# cpu.net
KiCad netlist of a schematic drawn in Altium Designer
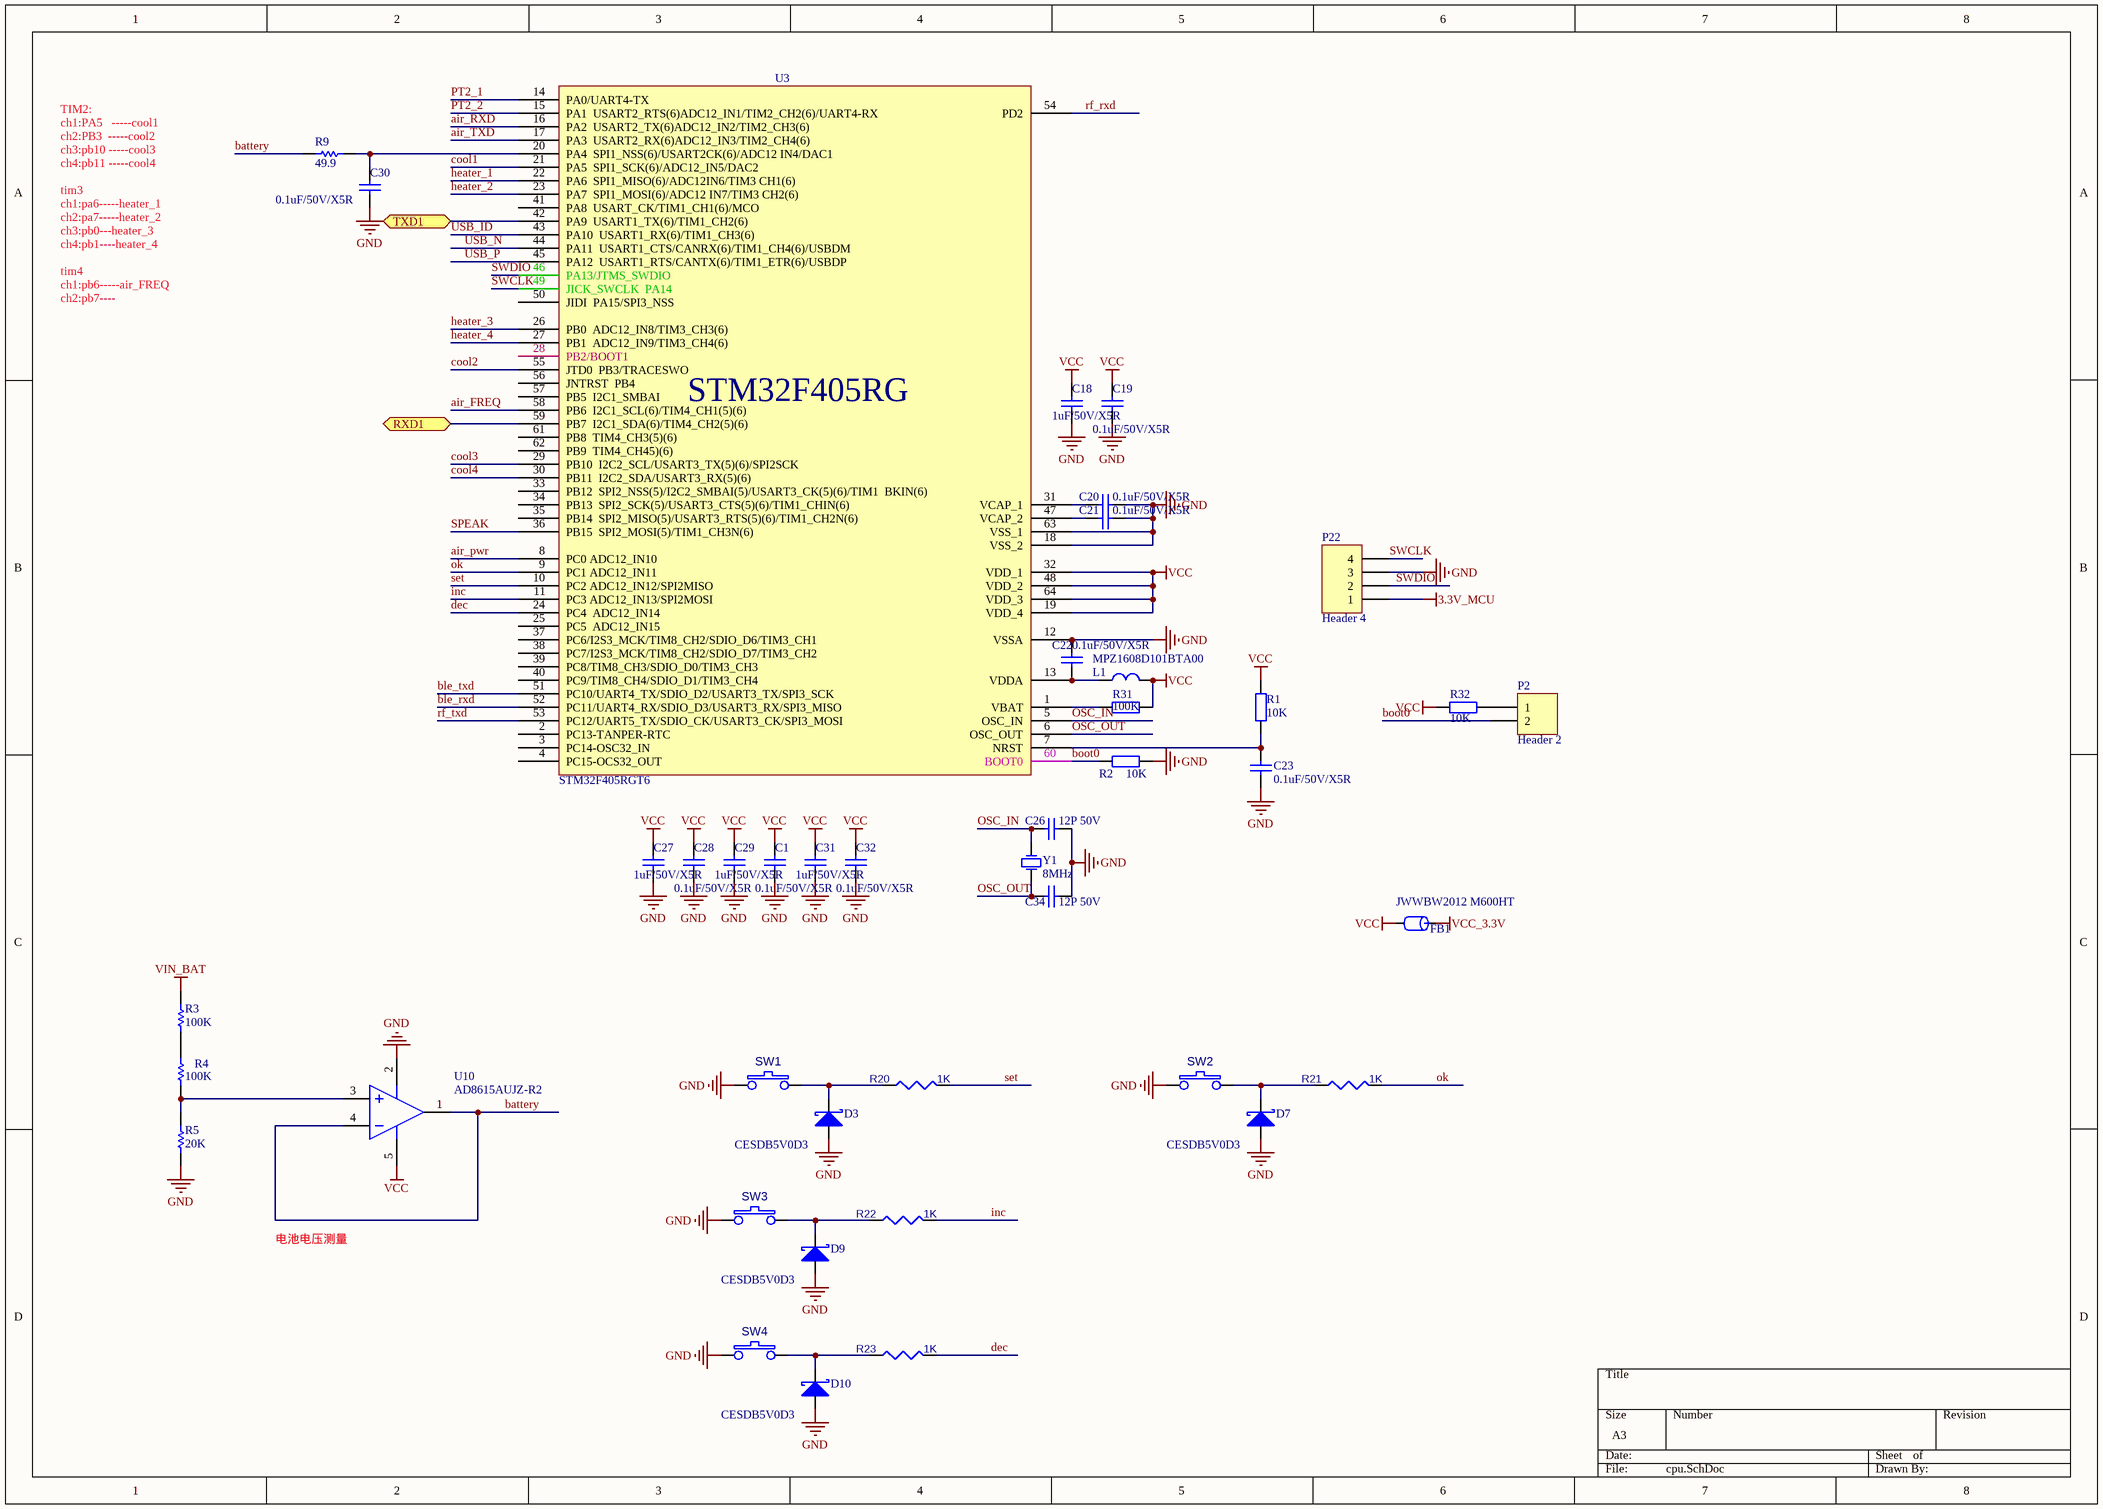
[diagram p0: cpu.SchDoc]

(export (version "E")
  (design (tool "Eeschema 10.0.6"))
  (components
    (comp (ref "C1")
      (value "0.1uF/50V/X5R")
      (footprint "0603C")
      (description "贴片电容 20%")
      (libsource (lib "XiaoyI") (part "CAP4"))
    )
    (comp (ref "C18")
      (value "1uF/50V/X5R")
      (footprint "0603C")
      (description "贴片电容 20%")
      (libsource (lib "XiaoyI") (part "CAP4"))
    )
    (comp (ref "C19")
      (value "0.1uF/50V/X5R")
      (footprint "0603C")
      (description "贴片电容 20%")
      (libsource (lib "XiaoyI") (part "CAP4"))
    )
    (comp (ref "C20")
      (value "0.1uF/50V/X5R")
      (footprint "0603C")
      (description "贴片电容 20%")
      (libsource (lib "XiaoyI") (part "CAP4"))
    )
    (comp (ref "C21")
      (value "0.1uF/50V/X5R")
      (footprint "0603C")
      (description "贴片电容 20%")
      (libsource (lib "XiaoyI") (part "CAP4"))
    )
    (comp (ref "C22")
      (value "0.1uF/50V/X5R")
      (footprint "0603C")
      (description "贴片电容 20%")
      (libsource (lib "XiaoyI") (part "CAP4"))
    )
    (comp (ref "C23")
      (value "0.1uF/50V/X5R")
      (footprint "0603C")
      (description "贴片电容 20%")
      (libsource (lib "XiaoyI") (part "CAP4"))
    )
    (comp (ref "C26")
      (value "12P 50V")
      (footprint "0603C")
      (description "贴片电容 20%")
      (libsource (lib "XiaoyI") (part "CAP4"))
    )
    (comp (ref "C27")
      (value "1uF/50V/X5R")
      (footprint "0603C")
      (description "贴片电容 20%")
      (libsource (lib "XiaoyI") (part "CAP4"))
    )
    (comp (ref "C28")
      (value "0.1uF/50V/X5R")
      (footprint "0603C")
      (description "贴片电容 20%")
      (libsource (lib "XiaoyI") (part "CAP4"))
    )
    (comp (ref "C29")
      (value "1uF/50V/X5R")
      (footprint "0603C")
      (description "贴片电容 20%")
      (libsource (lib "XiaoyI") (part "CAP4"))
    )
    (comp (ref "C30")
      (value "0.1uF/50V/X5R")
      (footprint "0603C")
      (description "贴片电容 20%")
      (libsource (lib "XiaoyI") (part "CAP4"))
    )
    (comp (ref "C31")
      (value "1uF/50V/X5R")
      (footprint "0603C")
      (description "贴片电容 20%")
      (libsource (lib "XiaoyI") (part "CAP4"))
    )
    (comp (ref "C32")
      (value "0.1uF/50V/X5R")
      (footprint "0603C")
      (description "贴片电容 20%")
      (libsource (lib "XiaoyI") (part "CAP4"))
    )
    (comp (ref "C34")
      (value "12P 50V")
      (footprint "0603C")
      (description "贴片电容 20%")
      (libsource (lib "XiaoyI") (part "CAP4"))
    )
    (comp (ref "D3")
      (value "CESDB5V0D3")
      (footprint "SOD323")
      (description "Schottky Diode")
      (libsource (lib "*") (part "DIODE S"))
    )
    (comp (ref "D7")
      (value "CESDB5V0D3")
      (footprint "SOD323")
      (description "Schottky Diode")
      (libsource (lib "*") (part "DIODE S"))
    )
    (comp (ref "D9")
      (value "CESDB5V0D3")
      (footprint "SOD323")
      (description "Schottky Diode")
      (libsource (lib "*") (part "DIODE S"))
    )
    (comp (ref "D10")
      (value "CESDB5V0D3")
      (footprint "SOD323")
      (description "Schottky Diode")
      (libsource (lib "*") (part "DIODE S"))
    )
    (comp (ref "FB1")
      (value "JWWBW2012 M600HT")
      (footprint "0805CZ")
      (libsource (lib "Schlib_20110825") (part "FB"))
    )
    (comp (ref "L1")
      (value "MPZ1608D101BTA00")
      (footprint "0603R")
      (description "磁珠电感 100R 100MHz")
      (libsource (lib "XiaoyI") (part "CIZHU1"))
    )
    (comp (ref "P2")
      (value "Header 2")
      (footprint "HDR1X2")
      (description "Header, 2-Pin")
      (fields (field (name "PUBLISHER") "Altium Limited"))
      (libsource (lib "Miscellaneous Connectors") (part "Header 2"))
    )
    (comp (ref "P22")
      (value "Header 4")
      (footprint "HDR1X4")
      (description "Header, 4-Pin")
      (fields (field (name "PUBLISHER") "Altium Limited"))
      (libsource (lib "Miscellaneous Connectors") (part "Header 4"))
    )
    (comp (ref "R1")
      (value "10K")
      (footprint "0603R")
      (description "贴片电阻 5%")
      (libsource (lib "") (part "RES2_2"))
    )
    (comp (ref "R2")
      (value "10K")
      (footprint "0603R")
      (description "贴片电阻 5%")
      (libsource (lib "XiaoyI") (part "RES2"))
    )
    (comp (ref "R3")
      (value "100K")
      (footprint "0603R")
      (description "Resistor")
      (fields (field (name "PUBLISHER") "Altium Limited"))
      (libsource (lib "Miscellaneous Devices") (part "Res1"))
    )
    (comp (ref "R4")
      (value "100K")
      (footprint "0603R")
      (description "Resistor")
      (fields (field (name "PUBLISHER") "Altium Limited"))
      (libsource (lib "Miscellaneous Devices") (part "Res1"))
    )
    (comp (ref "R5")
      (value "20K")
      (footprint "0603R")
      (description "Resistor")
      (fields (field (name "PUBLISHER") "Altium Limited"))
      (libsource (lib "Miscellaneous Devices") (part "Res1"))
    )
    (comp (ref "R9")
      (value "49.9")
      (footprint "0603R")
      (description "Resistor")
      (fields (field (name "PUBLISHER") "Altium Limited"))
      (libsource (lib "Miscellaneous Devices") (part "Res1"))
    )
    (comp (ref "R20")
      (value "1K")
      (footprint "0603R")
      (fields (field (name "Comment") "1k/1%"))
      (libsource (lib "*") (part "RESISTOR_0"))
    )
    (comp (ref "R21")
      (value "1K")
      (footprint "0603R")
      (fields (field (name "Comment") "1k/1%"))
      (libsource (lib "*") (part "RESISTOR_0"))
    )
    (comp (ref "R22")
      (value "1K")
      (footprint "0603R")
      (fields (field (name "Comment") "1k/1%"))
      (libsource (lib "*") (part "RESISTOR_0"))
    )
    (comp (ref "R23")
      (value "1K")
      (footprint "0603R")
      (fields (field (name "Comment") "1k/1%"))
      (libsource (lib "*") (part "RESISTOR_0"))
    )
    (comp (ref "R31")
      (value "100K")
      (footprint "0603R")
      (description "贴片电阻 5%")
      (libsource (lib "") (part "RES2_1"))
    )
    (comp (ref "R32")
      (value "10K")
      (footprint "0603R")
      (description "贴片电阻 5%")
      (libsource (lib "") (part "RES2_1"))
    )
    (comp (ref "SW1")
      (value "SW PUSHBUTTON")
      (footprint "SW-SMD_L3.9-W3.0-P4.45")
      (libsource (lib "*") (part "SW PUSHBUTTON"))
    )
    (comp (ref "SW2")
      (value "SW PUSHBUTTON")
      (footprint "SW-SMD_L3.9-W3.0-P4.45")
      (libsource (lib "*") (part "SW PUSHBUTTON"))
    )
    (comp (ref "SW3")
      (value "SW PUSHBUTTON")
      (footprint "SW-SMD_L3.9-W3.0-P4.45")
      (libsource (lib "*") (part "SW PUSHBUTTON"))
    )
    (comp (ref "SW4")
      (value "SW PUSHBUTTON")
      (footprint "SW-SMD_L3.9-W3.0-P4.45")
      (libsource (lib "*") (part "SW PUSHBUTTON"))
    )
    (comp (ref "U3")
      (value "STM32F405RGT6")
      (footprint "LQFP-64")
      (description "MCU")
      (libsource (lib "XiaoyI") (part "STM32F405RG"))
    )
    (comp (ref "U10")
      (value "AD8615AUJZ-R2")
      (footprint "sot-23-5")
      (libsource (lib "Schlib1") (part "AD8615"))
    )
    (comp (ref "Y1")
      (value "8MHz")
      (footprint "CRAY_5032")
      (description "晶振")
      (libsource (lib "XiaoyI") (part "XTAL"))
    )
  )
  (nets
    (net (code "1") (name "/OSC_IN") (class "Default")
      (node (ref "C26") (pin "2") (pinfunction "2_2") (pintype "passive"))
      (node (ref "U3") (pin "5") (pinfunction "OSC_IN_5") (pintype "passive"))
      (node (ref "Y1") (pin "2") (pinfunction "OSC2_2") (pintype "passive"))
    )
    (net (code "2") (name "/OSC_OUT") (class "Default")
      (node (ref "C34") (pin "2") (pinfunction "2_2") (pintype "passive"))
      (node (ref "U3") (pin "6") (pinfunction "OSC_OUT_6") (pintype "passive"))
      (node (ref "Y1") (pin "1") (pinfunction "OSC1_1") (pintype "passive"))
    )
    (net (code "3") (name "/PT2_1") (class "Default")
      (node (ref "U3") (pin "14") (pinfunction "PA0/UART4-TX_14") (pintype "passive"))
    )
    (net (code "4") (name "/PT2_2") (class "Default")
      (node (ref "U3") (pin "15") (pinfunction "PA1__USART2_RTS(6)ADC12_IN1/TIM2_CH2(6)/UART4-RX_15") (pintype "passive"))
    )
    (net (code "5") (name "/RXD1") (class "Default")
      (node (ref "U3") (pin "59") (pinfunction "PB7__I2C1_SDA(6)/TIM4_CH2(5)(6)_59") (pintype "passive"))
    )
    (net (code "6") (name "/SPEAK") (class "Default")
      (node (ref "U3") (pin "36") (pinfunction "PB15__SPI2_MOSI(5)/TIM1_CH3N(6)_36") (pintype "passive"))
    )
    (net (code "7") (name "/SWCLK") (class "Default")
      (node (ref "P22") (pin "4") (pinfunction "4_4") (pintype "passive"))
      (node (ref "U3") (pin "49") (pinfunction "JICK_SWCLK__PA14_49") (pintype "passive"))
    )
    (net (code "8") (name "/SWDIO") (class "Default")
      (node (ref "P22") (pin "2") (pinfunction "2_2") (pintype "passive"))
      (node (ref "U3") (pin "46") (pinfunction "PA13/JTMS_SWDIO_46") (pintype "passive"))
    )
    (net (code "9") (name "/TXD1") (class "Default")
      (node (ref "U3") (pin "42") (pinfunction "PA9__USART1_TX(6)/TIM1_CH2(6)_42") (pintype "passive"))
    )
    (net (code "10") (name "/USB_ID") (class "Default")
      (node (ref "U3") (pin "43") (pinfunction "PA10__USART1_RX(6)/TIM1_CH3(6)_43") (pintype "passive"))
    )
    (net (code "11") (name "/USB_N") (class "Default")
      (node (ref "U3") (pin "44") (pinfunction "PA11__USART1_CTS/CANRX(6)/TIM1_CH4(6)/USBDM_44") (pintype "passive"))
    )
    (net (code "12") (name "/USB_P") (class "Default")
      (node (ref "U3") (pin "45") (pinfunction "PA12__USART1_RTS/CANTX(6)/TIM1_ETR(6)/USBDP_45") (pintype "passive"))
    )
    (net (code "13") (name "/air_FREQ") (class "Default")
      (node (ref "U3") (pin "58") (pinfunction "PB6__I2C1_SCL(6)/TIM4_CH1(5)(6)_58") (pintype "passive"))
    )
    (net (code "14") (name "/air_RXD") (class "Default")
      (node (ref "U3") (pin "16") (pinfunction "PA2__USART2_TX(6)ADC12_IN2/TIM2_CH3(6)_16") (pintype "passive"))
    )
    (net (code "15") (name "/air_TXD") (class "Default")
      (node (ref "U3") (pin "17") (pinfunction "PA3__USART2_RX(6)ADC12_IN3/TIM2_CH4(6)_17") (pintype "passive"))
    )
    (net (code "16") (name "/air_pwr") (class "Default")
      (node (ref "U3") (pin "8") (pinfunction "PC0_ADC12_IN10_8") (pintype "passive"))
    )
    (net (code "17") (name "/battery") (class "Default")
      (node (ref "R9") (pin "1") (pinfunction "1_1") (pintype "passive"))
      (node (ref "U10") (pin "1") (pinfunction "OS_NUL_1") (pintype "passive"))
      (node (ref "U10") (pin "4") (pinfunction "V-_4") (pintype "power_in"))
    )
    (net (code "18") (name "/ble_rxd") (class "Default")
      (node (ref "U3") (pin "52") (pinfunction "PC11/UART4_RX/SDIO_D3/USART3_RX/SPI3_MISO_52") (pintype "passive"))
    )
    (net (code "19") (name "/ble_txd") (class "Default")
      (node (ref "U3") (pin "51") (pinfunction "PC10/UART4_TX/SDIO_D2/USART3_TX/SPI3_SCK_51") (pintype "passive"))
    )
    (net (code "20") (name "/boot0") (class "Default")
      (node (ref "P2") (pin "2") (pinfunction "2_2") (pintype "passive"))
      (node (ref "R2") (pin "1") (pinfunction "1_1") (pintype "passive"))
      (node (ref "U3") (pin "60") (pinfunction "BOOT0_60") (pintype "passive"))
    )
    (net (code "21") (name "/cool1") (class "Default")
      (node (ref "U3") (pin "21") (pinfunction "PA5__SPI1_SCK(6)/ADC12_IN5/DAC2_21") (pintype "passive"))
    )
    (net (code "22") (name "/cool2") (class "Default")
      (node (ref "U3") (pin "55") (pinfunction "JTD0__PB3/TRACESWO_55") (pintype "passive"))
    )
    (net (code "23") (name "/cool3") (class "Default")
      (node (ref "U3") (pin "29") (pinfunction "PB10__I2C2_SCL/USART3_TX(5)(6)/SPI2SCK_29") (pintype "passive"))
    )
    (net (code "24") (name "/cool4") (class "Default")
      (node (ref "U3") (pin "30") (pinfunction "PB11__I2C2_SDA/USART3_RX(5)(6)_30") (pintype "passive"))
    )
    (net (code "25") (name "/dec") (class "Default")
      (node (ref "R23") (pin "2") (pinfunction "2_2") (pintype "passive"))
      (node (ref "U3") (pin "24") (pinfunction "PC4__ADC12_IN14_24") (pintype "passive"))
    )
    (net (code "26") (name "/heater_1") (class "Default")
      (node (ref "U3") (pin "22") (pinfunction "PA6__SPI1_MISO(6)/ADC12IN6/TIM3_CH1(6)_22") (pintype "passive"))
    )
    (net (code "27") (name "/heater_2") (class "Default")
      (node (ref "U3") (pin "23") (pinfunction "PA7__SPI1_MOSI(6)/ADC12_IN7/TIM3_CH2(6)_23") (pintype "passive"))
    )
    (net (code "28") (name "/heater_3") (class "Default")
      (node (ref "U3") (pin "26") (pinfunction "PB0__ADC12_IN8/TIM3_CH3(6)_26") (pintype "passive"))
    )
    (net (code "29") (name "/heater_4") (class "Default")
      (node (ref "U3") (pin "27") (pinfunction "PB1__ADC12_IN9/TIM3_CH4(6)_27") (pintype "passive"))
    )
    (net (code "30") (name "/inc") (class "Default")
      (node (ref "R22") (pin "2") (pinfunction "2_2") (pintype "passive"))
      (node (ref "U3") (pin "11") (pinfunction "PC3_ADC12_IN13/SPI2MOSI_11") (pintype "passive"))
    )
    (net (code "31") (name "/ok") (class "Default")
      (node (ref "R21") (pin "2") (pinfunction "2_2") (pintype "passive"))
      (node (ref "U3") (pin "9") (pinfunction "PC1_ADC12_IN11_9") (pintype "passive"))
    )
    (net (code "32") (name "/rf_rxd") (class "Default")
      (node (ref "U3") (pin "54") (pinfunction "PD2_54") (pintype "passive"))
    )
    (net (code "33") (name "/rf_txd") (class "Default")
      (node (ref "U3") (pin "53") (pinfunction "PC12/UART5_TX/SDIO_CK/USART3_CK/SPI3_MOSI_53") (pintype "passive"))
    )
    (net (code "34") (name "/set") (class "Default")
      (node (ref "R20") (pin "2") (pinfunction "2_2") (pintype "passive"))
      (node (ref "U3") (pin "10") (pinfunction "PC2_ADC12_IN12/SPI2MISO_10") (pintype "passive"))
    )
    (net (code "35") (name "3.3V_MCU") (class "Default")
      (node (ref "P22") (pin "1") (pinfunction "1_1") (pintype "passive"))
    )
    (net (code "36") (name "GND") (class "Default")
      (node (ref "C1") (pin "1") (pinfunction "1_1") (pintype "passive"))
      (node (ref "C18") (pin "1") (pinfunction "1_1") (pintype "passive"))
      (node (ref "C19") (pin "1") (pinfunction "1_1") (pintype "passive"))
      (node (ref "C20") (pin "1") (pinfunction "1_1") (pintype "passive"))
      (node (ref "C21") (pin "1") (pinfunction "1_1") (pintype "passive"))
      (node (ref "C22") (pin "1") (pinfunction "1_1") (pintype "passive"))
      (node (ref "C23") (pin "1") (pinfunction "1_1") (pintype "passive"))
      (node (ref "C26") (pin "1") (pinfunction "1_1") (pintype "passive"))
      (node (ref "C27") (pin "1") (pinfunction "1_1") (pintype "passive"))
      (node (ref "C28") (pin "1") (pinfunction "1_1") (pintype "passive"))
      (node (ref "C29") (pin "1") (pinfunction "1_1") (pintype "passive"))
      (node (ref "C30") (pin "1") (pinfunction "1_1") (pintype "passive"))
      (node (ref "C31") (pin "1") (pinfunction "1_1") (pintype "passive"))
      (node (ref "C32") (pin "1") (pinfunction "1_1") (pintype "passive"))
      (node (ref "C34") (pin "1") (pinfunction "1_1") (pintype "passive"))
      (node (ref "D10") (pin "1") (pinfunction "A_1") (pintype "passive"))
      (node (ref "D3") (pin "1") (pinfunction "A_1") (pintype "passive"))
      (node (ref "D7") (pin "1") (pinfunction "A_1") (pintype "passive"))
      (node (ref "D9") (pin "1") (pinfunction "A_1") (pintype "passive"))
      (node (ref "P22") (pin "3") (pinfunction "3_3") (pintype "passive"))
      (node (ref "R2") (pin "2") (pinfunction "2_2") (pintype "passive"))
      (node (ref "R5") (pin "2") (pinfunction "2_2") (pintype "passive"))
      (node (ref "SW1") (pin "1") (pinfunction "1_1") (pintype "passive"))
      (node (ref "SW2") (pin "1") (pinfunction "1_1") (pintype "passive"))
      (node (ref "SW3") (pin "1") (pinfunction "1_1") (pintype "passive"))
      (node (ref "SW4") (pin "1") (pinfunction "1_1") (pintype "passive"))
      (node (ref "U10") (pin "2") (pinfunction "G_2") (pintype "power_in"))
      (node (ref "U3") (pin "12") (pinfunction "VSSA_12") (pintype "passive"))
      (node (ref "U3") (pin "18") (pinfunction "VSS_2_18") (pintype "passive"))
      (node (ref "U3") (pin "63") (pinfunction "VSS_1_63") (pintype "passive"))
    )
    (net (code "37") (name "Net-(D3-K)") (class "Default")
      (node (ref "D3") (pin "2") (pinfunction "K_2") (pintype "passive"))
      (node (ref "R20") (pin "1") (pinfunction "1_1") (pintype "passive"))
      (node (ref "SW1") (pin "2") (pinfunction "2_2") (pintype "passive"))
    )
    (net (code "38") (name "Net-(D7-K)") (class "Default")
      (node (ref "D7") (pin "2") (pinfunction "K_2") (pintype "passive"))
      (node (ref "R21") (pin "1") (pinfunction "1_1") (pintype "passive"))
      (node (ref "SW2") (pin "2") (pinfunction "2_2") (pintype "passive"))
    )
    (net (code "39") (name "Net-(D9-K)") (class "Default")
      (node (ref "D9") (pin "2") (pinfunction "K_2") (pintype "passive"))
      (node (ref "R22") (pin "1") (pinfunction "1_1") (pintype "passive"))
      (node (ref "SW3") (pin "2") (pinfunction "2_2") (pintype "passive"))
    )
    (net (code "40") (name "Net-(D10-K)") (class "Default")
      (node (ref "D10") (pin "2") (pinfunction "K_2") (pintype "passive"))
      (node (ref "R23") (pin "1") (pinfunction "1_1") (pintype "passive"))
      (node (ref "SW4") (pin "2") (pinfunction "2_2") (pintype "passive"))
    )
    (net (code "41") (name "Net-(P2-Pad1)") (class "Default")
      (node (ref "P2") (pin "1") (pinfunction "1_1") (pintype "passive"))
      (node (ref "R32") (pin "1") (pinfunction "1_1") (pintype "passive"))
    )
    (net (code "42") (name "Net-(R3-Pad2)") (class "Default")
      (node (ref "R3") (pin "2") (pinfunction "2_2") (pintype "passive"))
      (node (ref "R4") (pin "1") (pinfunction "1_1") (pintype "passive"))
    )
    (net (code "43") (name "Net-(U3-NRST)") (class "Default")
      (node (ref "C23") (pin "2") (pinfunction "2_2") (pintype "passive"))
      (node (ref "R1") (pin "2") (pinfunction "2_2") (pintype "passive"))
      (node (ref "U3") (pin "7") (pinfunction "NRST_7") (pintype "passive"))
    )
    (net (code "44") (name "Net-(U3-PA4__SPI1_NSS(6){slash}USART2CK(6){slash}ADC12_IN4{slash}DAC1)") (class "Default")
      (node (ref "C30") (pin "2") (pinfunction "2_2") (pintype "passive"))
      (node (ref "R9") (pin "2") (pinfunction "2_2") (pintype "passive"))
      (node (ref "U3") (pin "20") (pinfunction "PA4__SPI1_NSS(6)/USART2CK(6)/ADC12_IN4/DAC1_20") (pintype "passive"))
    )
    (net (code "45") (name "Net-(U3-VBAT)") (class "Default")
      (node (ref "R31") (pin "2") (pinfunction "2_2") (pintype "passive"))
      (node (ref "U3") (pin "1") (pinfunction "VBAT_1") (pintype "passive"))
    )
    (net (code "46") (name "Net-(U3-VCAP_1)") (class "Default")
      (node (ref "C20") (pin "2") (pinfunction "2_2") (pintype "passive"))
      (node (ref "U3") (pin "31") (pinfunction "VCAP_1_31") (pintype "passive"))
    )
    (net (code "47") (name "Net-(U3-VCAP_2)") (class "Default")
      (node (ref "C21") (pin "2") (pinfunction "2_2") (pintype "passive"))
      (node (ref "U3") (pin "47") (pinfunction "VCAP_2_47") (pintype "passive"))
    )
    (net (code "48") (name "Net-(U3-VDDA)") (class "Default")
      (node (ref "C22") (pin "2") (pinfunction "2_2") (pintype "passive"))
      (node (ref "L1") (pin "1") (pinfunction "1_1") (pintype "passive"))
      (node (ref "U3") (pin "13") (pinfunction "VDDA_13") (pintype "passive"))
    )
    (net (code "49") (name "Net-(U10-V+)") (class "Default")
      (node (ref "R4") (pin "2") (pinfunction "2_2") (pintype "passive"))
      (node (ref "R5") (pin "1") (pinfunction "1_1") (pintype "passive"))
      (node (ref "U10") (pin "3") (pinfunction "V+_3") (pintype "power_in"))
    )
    (net (code "50") (name "VCC") (class "Default")
      (node (ref "C1") (pin "2") (pinfunction "2_2") (pintype "passive"))
      (node (ref "C18") (pin "2") (pinfunction "2_2") (pintype "passive"))
      (node (ref "C19") (pin "2") (pinfunction "2_2") (pintype "passive"))
      (node (ref "C27") (pin "2") (pinfunction "2_2") (pintype "passive"))
      (node (ref "C28") (pin "2") (pinfunction "2_2") (pintype "passive"))
      (node (ref "C29") (pin "2") (pinfunction "2_2") (pintype "passive"))
      (node (ref "C31") (pin "2") (pinfunction "2_2") (pintype "passive"))
      (node (ref "C32") (pin "2") (pinfunction "2_2") (pintype "passive"))
      (node (ref "FB1") (pin "2") (pintype "passive"))
      (node (ref "L1") (pin "2") (pinfunction "2_2") (pintype "passive"))
      (node (ref "R1") (pin "1") (pinfunction "1_1") (pintype "passive"))
      (node (ref "R31") (pin "1") (pinfunction "1_1") (pintype "passive"))
      (node (ref "R32") (pin "2") (pinfunction "2_2") (pintype "passive"))
      (node (ref "U10") (pin "5") (pinfunction "VCC_5") (pintype "passive"))
      (node (ref "U3") (pin "19") (pinfunction "VDD_4_19") (pintype "passive"))
      (node (ref "U3") (pin "32") (pinfunction "VDD_1_32") (pintype "passive"))
      (node (ref "U3") (pin "48") (pinfunction "VDD_2_48") (pintype "passive"))
      (node (ref "U3") (pin "64") (pinfunction "VDD_3_64") (pintype "passive"))
    )
    (net (code "51") (name "VCC_3.3V") (class "Default") (node (ref "FB1") (pin "1") (pintype "passive")))
    (net (code "52") (name "VIN_BAT") (class "Default")
      (node (ref "R3") (pin "1") (pinfunction "1_1") (pintype "passive"))
    )
    (net (code "53") (name "unconnected-(U3-JIDI__PA15{slash}SPI3_NSS-Pad50)") (class "Default")
      (node (ref "U3") (pin "50") (pinfunction "JIDI__PA15/SPI3_NSS_50") (pintype "passive"))
    )
    (net (code "54") (name "unconnected-(U3-JNTRST__PB4-Pad56)") (class "Default")
      (node (ref "U3") (pin "56") (pinfunction "JNTRST__PB4_56") (pintype "passive"))
    )
    (net (code "55") (name "unconnected-(U3-PA8__USART_CK{slash}TIM1_CH1(6){slash}MCO-Pad41)") (class "Default")
      (node (ref "U3") (pin "41") (pinfunction "PA8__USART_CK/TIM1_CH1(6)/MCO_41") (pintype "passive"))
    )
    (net (code "56") (name "unconnected-(U3-PB2{slash}BOOT1-Pad28)") (class "Default")
      (node (ref "U3") (pin "28") (pinfunction "PB2/BOOT1_28") (pintype "passive"))
    )
    (net (code "57") (name "unconnected-(U3-PB5__I2C1_SMBAI-Pad57)") (class "Default")
      (node (ref "U3") (pin "57") (pinfunction "PB5__I2C1_SMBAI_57") (pintype "passive"))
    )
    (net (code "58") (name "unconnected-(U3-PB8__TIM4_CH3(5)(6)-Pad61)") (class "Default")
      (node (ref "U3") (pin "61") (pinfunction "PB8__TIM4_CH3(5)(6)_61") (pintype "passive"))
    )
    (net (code "59") (name "unconnected-(U3-PB9__TIM4_CH45)(6)-Pad62)") (class "Default")
      (node (ref "U3") (pin "62") (pinfunction "PB9__TIM4_CH45)(6)_62") (pintype "passive"))
    )
    (net (code "60") (name "unconnected-(U3-PB12__SPI2_NSS(5){slash}I2C2_SMBAI(5){slash}USART3_CK(5)(6){slash}TIM1__BKIN(6)-Pad33)") (class "Default")
      (node (ref "U3") (pin "33") (pinfunction "PB12__SPI2_NSS(5)/I2C2_SMBAI(5)/USART3_CK(5)(6)/TIM1__BKIN(6)_33") (pintype "passive"))
    )
    (net (code "61") (name "unconnected-(U3-PB13__SPI2_SCK(5){slash}USART3_CTS(5)(6){slash}TIM1_CHIN(6)-Pad34)") (class "Default")
      (node (ref "U3") (pin "34") (pinfunction "PB13__SPI2_SCK(5)/USART3_CTS(5)(6)/TIM1_CHIN(6)_34") (pintype "passive"))
    )
    (net (code "62") (name "unconnected-(U3-PB14__SPI2_MISO(5){slash}USART3_RTS(5)(6){slash}TIM1_CH2N(6)-Pad35)") (class "Default")
      (node (ref "U3") (pin "35") (pinfunction "PB14__SPI2_MISO(5)/USART3_RTS(5)(6)/TIM1_CH2N(6)_35") (pintype "passive"))
    )
    (net (code "63") (name "unconnected-(U3-PC5__ADC12_IN15-Pad25)") (class "Default")
      (node (ref "U3") (pin "25") (pinfunction "PC5__ADC12_IN15_25") (pintype "passive"))
    )
    (net (code "64") (name "unconnected-(U3-PC6{slash}I2S3_MCK{slash}TIM8_CH2{slash}SDIO_D6{slash}TIM3_CH1-Pad37)") (class "Default")
      (node (ref "U3") (pin "37") (pinfunction "PC6/I2S3_MCK/TIM8_CH2/SDIO_D6/TIM3_CH1_37") (pintype "passive"))
    )
    (net (code "65") (name "unconnected-(U3-PC7{slash}I2S3_MCK{slash}TIM8_CH2{slash}SDIO_D7{slash}TIM3_CH2-Pad38)") (class "Default")
      (node (ref "U3") (pin "38") (pinfunction "PC7/I2S3_MCK/TIM8_CH2/SDIO_D7/TIM3_CH2_38") (pintype "passive"))
    )
    (net (code "66") (name "unconnected-(U3-PC8{slash}TIM8_CH3{slash}SDIO_D0{slash}TIM3_CH3-Pad39)") (class "Default")
      (node (ref "U3") (pin "39") (pinfunction "PC8/TIM8_CH3/SDIO_D0/TIM3_CH3_39") (pintype "passive"))
    )
    (net (code "67") (name "unconnected-(U3-PC9{slash}TIM8_CH4{slash}SDIO_D1{slash}TIM3_CH4-Pad40)") (class "Default")
      (node (ref "U3") (pin "40") (pinfunction "PC9/TIM8_CH4/SDIO_D1/TIM3_CH4_40") (pintype "passive"))
    )
    (net (code "68") (name "unconnected-(U3-PC13-TANPER-RTC-Pad2)") (class "Default")
      (node (ref "U3") (pin "2") (pinfunction "PC13-TANPER-RTC_2") (pintype "passive"))
    )
    (net (code "69") (name "unconnected-(U3-PC14-OSC32_IN-Pad3)") (class "Default")
      (node (ref "U3") (pin "3") (pinfunction "PC14-OSC32_IN_3") (pintype "passive"))
    )
    (net (code "70") (name "unconnected-(U3-PC15-OCS32_OUT-Pad4)") (class "Default")
      (node (ref "U3") (pin "4") (pinfunction "PC15-OCS32_OUT_4") (pintype "passive"))
    )
  )
)
